# Analog_Input.net
KiCad netlist of a schematic drawn in Altium Designer
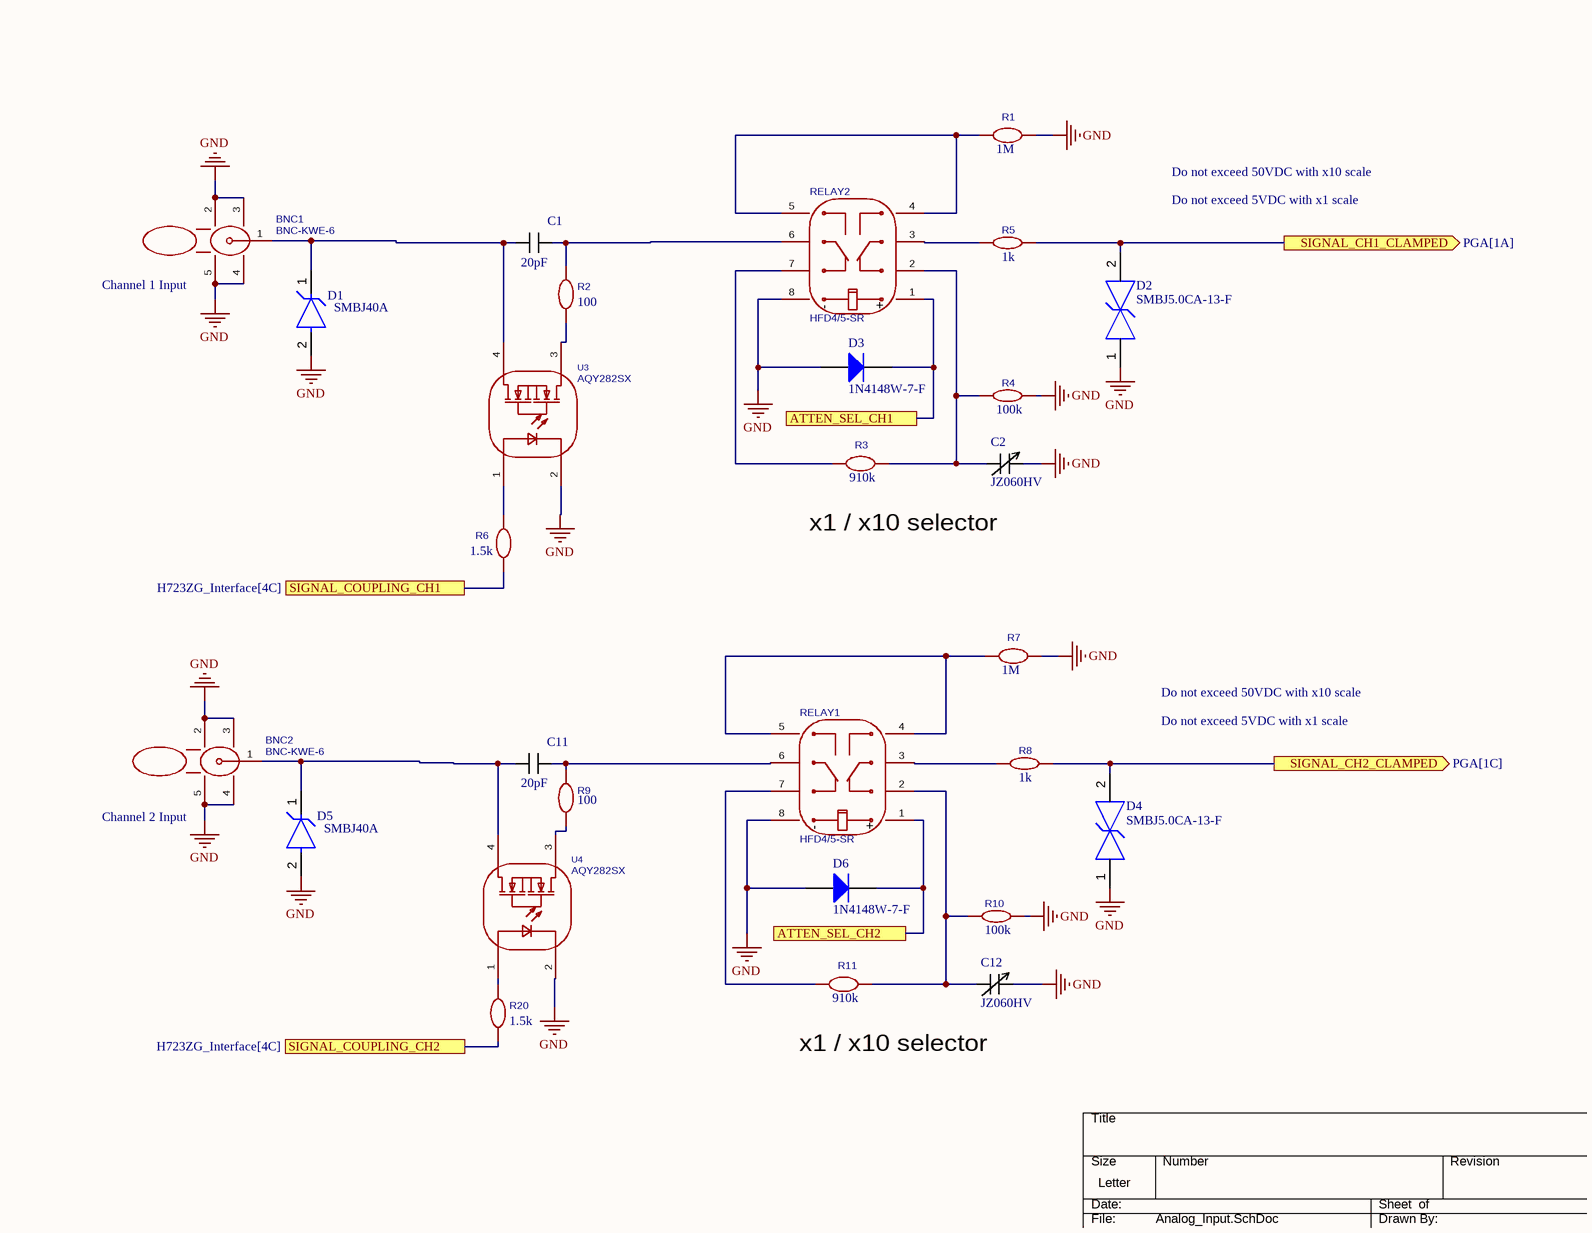
[diagram p0: Analog_Input.SchDoc]

(export (version "E")
  (design (tool "Eeschema 10.0.6"))
  (components
    (comp (ref "BNC1")
      (value "BNC-KWE-6")
      (footprint "CONN-TH_BNC-KWE-6")
      (fields (field (name "MANUFACTURER") "cntitle(中戈泰斗)"))
      (libsource (lib "zhiming xue") (part "BNC-KWE-6"))
    )
    (comp (ref "BNC2")
      (value "BNC-KWE-6")
      (footprint "CONN-TH_BNC-KWE-6")
      (fields (field (name "MANUFACTURER") "cntitle(中戈泰斗)"))
      (libsource (lib "zhiming xue") (part "BNC-KWE-6"))
    )
    (comp (ref "C1")
      (value "20pF")
      (footprint "CAPCP2012X150N")
      (description "Mlcc 20PF ±5% C0G(NP0) 50V 0805")
      (fields
        (field (name "MANUFACTURER") "CCTC")
        (field (name "MANUFACTURER PART NUMBER") "TCC0805COG200J500BT")
      )
      (libsource (lib "zhiming xue") (part "Capacitor"))
    )
    (comp (ref "C2")
      (value "JZ060HV")
      (footprint "CAPCP4914X60N")
      (description "Variable Capacitor, 350V, 2pF Min, 6pF Max, Vertical Adjuster, Surface Mount")
      (libsource (lib "zhiming xue") (part "JZ060HV 2 - 6pF"))
    )
    (comp (ref "C11")
      (value "20pF")
      (footprint "CAPCP2012X150N")
      (description "Mlcc 20PF ±5% C0G(NP0) 50V 0805")
      (fields
        (field (name "MANUFACTURER") "CCTC")
        (field (name "MANUFACTURER PART NUMBER") "TCC0805COG200J500BT")
      )
      (libsource (lib "zhiming xue") (part "Capacitor"))
    )
    (comp (ref "C12")
      (value "JZ060HV")
      (footprint "CAPCP4914X60N")
      (description "Variable Capacitor, 350V, 2pF Min, 6pF Max, Vertical Adjuster, Surface Mount")
      (libsource (lib "zhiming xue") (part "JZ060HV 2 - 6pF"))
    )
    (comp (ref "D1")
      (value "SMBJ40A")
      (footprint "FP-SMBJ-MFG")
      (description "TVS DIODE 40VWM 64.5VC DO214AA")
      (libsource (lib "Altium Content Vault") (part "f813f71cba58e380607f5dd3caf9714"))
    )
    (comp (ref "D2")
      (value "SMBJ5.0CA-13-F")
      (footprint "FP-SMB-CA-MFG")
      (description "TVS DIODE 5V 9.2V SMB")
      (fields
        (field (name "MANUFACTURER") "Diodes Inc")
        (field (name "OCTOPART") "https://octopart.com/smbj5.0ca-13-f-diodes+inc.-13025192")
      )
      (libsource (lib "Altium Content Vault") (part "876f4347bf90aa6f500f43e3cd03972"))
    )
    (comp (ref "D3")
      (value "1N4148W-7-F")
      (footprint "DIOD-SOD123-2_V")
      (description "Fast Switching Diode, 100 V, 0.15 A, -65 to 150 degC, 2-Pin?SOD123, RoHS, Tape and Reel")
      (fields (field (name "MANUFACTURER") "Diodes Inc"))
      (libsource (lib "Altium Content Vault") (part "D-AK-2"))
    )
    (comp (ref "D4")
      (value "SMBJ5.0CA-13-F")
      (footprint "FP-SMB-CA-MFG")
      (description "TVS DIODE 5V 9.2V SMB")
      (fields
        (field (name "MANUFACTURER") "Diodes Inc")
        (field (name "OCTOPART") "https://octopart.com/smbj5.0ca-13-f-diodes+inc.-13025192")
      )
      (libsource (lib "Altium Content Vault") (part "876f4347bf90aa6f500f43e3cd03972"))
    )
    (comp (ref "D5")
      (value "SMBJ40A")
      (footprint "FP-SMBJ-MFG")
      (description "TVS DIODE 40VWM 64.5VC DO214AA")
      (libsource (lib "Altium Content Vault") (part "f813f71cba58e380607f5dd3caf9714"))
    )
    (comp (ref "D6")
      (value "1N4148W-7-F")
      (footprint "DIOD-SOD123-2_V")
      (description "Fast Switching Diode, 100 V, 0.15 A, -65 to 150 degC, 2-Pin?SOD123, RoHS, Tape and Reel")
      (fields (field (name "MANUFACTURER") "Diodes Inc"))
      (libsource (lib "Altium Content Vault") (part "D-AK-2"))
    )
    (comp (ref "R1")
      (value "1M")
      (footprint "R0805")
      (fields
        (field (name "MANUFACTURER") "FOJAN(富捷)")
        (field (name "TOLERANCE") "1%")
        (field (name "MANUFACTURER PART NUMBER") "FRC0805F1004TS")
      )
      (libsource (lib "zhiming xue") (part "RT0805BRD0710K1L"))
    )
    (comp (ref "R2")
      (value "100")
      (footprint "R0805")
      (fields
        (field (name "MANUFACTURER") "FOJAN(富捷)")
        (field (name "TOLERANCE") "1%")
        (field (name "MANUFACTURER PART NUMBER") "FRC0805F1000TS")
      )
      (libsource (lib "zhiming xue") (part "RT0805BRD0710K1L"))
    )
    (comp (ref "R3")
      (value "910k")
      (footprint "R0805")
      (fields
        (field (name "MANUFACTURER") "FOJAN(富捷)")
        (field (name "TOLERANCE") "1%")
        (field (name "MANUFACTURER PART NUMBER") "FRC0805F9103TS")
      )
      (libsource (lib "zhiming xue") (part "RT0805BRD0710K1L"))
    )
    (comp (ref "R4")
      (value "100k")
      (footprint "R0805")
      (fields
        (field (name "MANUFACTURER") "UNI-ROYAL(厚声)")
        (field (name "TOLERANCE") "1%")
        (field (name "MANUFACTURER PART NUMBER") "0805W8F1003T5E")
      )
      (libsource (lib "zhiming xue") (part "0805W8F0000T5E_C17477"))
    )
    (comp (ref "R5")
      (value "1k")
      (footprint "R0805")
      (fields
        (field (name "MANUFACTURER") "UNI-ROYAL(厚声)")
        (field (name "TOLERANCE") "1%")
        (field (name "MANUFACTURER PART NUMBER") "0805W8F1001T5E")
      )
      (libsource (lib "zhiming xue") (part "0805W8F0000T5E_C17477"))
    )
    (comp (ref "R6")
      (value "1.5k")
      (footprint "R0805")
      (fields
        (field (name "MANUFACTURER") "FOJAN(富捷)")
        (field (name "TOLERANCE") "1%")
        (field (name "MANUFACTURER PART NUMBER") "FRC0805F1501TS")
      )
      (libsource (lib "zhiming xue") (part "RT0805BRD0710K1L"))
    )
    (comp (ref "R7")
      (value "1M")
      (footprint "R0805")
      (fields
        (field (name "MANUFACTURER") "FOJAN(富捷)")
        (field (name "TOLERANCE") "1%")
        (field (name "MANUFACTURER PART NUMBER") "FRC0805F1004TS")
      )
      (libsource (lib "zhiming xue") (part "RT0805BRD0710K1L"))
    )
    (comp (ref "R8")
      (value "1k")
      (footprint "R0805")
      (fields
        (field (name "MANUFACTURER") "UNI-ROYAL(厚声)")
        (field (name "TOLERANCE") "1%")
        (field (name "MANUFACTURER PART NUMBER") "0805W8F1001T5E")
      )
      (libsource (lib "zhiming xue") (part "0805W8F0000T5E_C17477"))
    )
    (comp (ref "R9")
      (value "100")
      (footprint "R0805")
      (fields
        (field (name "MANUFACTURER") "FOJAN(富捷)")
        (field (name "TOLERANCE") "1%")
        (field (name "MANUFACTURER PART NUMBER") "FRC0805F1000TS")
      )
      (libsource (lib "zhiming xue") (part "RT0805BRD0710K1L"))
    )
    (comp (ref "R10")
      (value "100k")
      (footprint "R0805")
      (fields
        (field (name "MANUFACTURER") "UNI-ROYAL(厚声)")
        (field (name "TOLERANCE") "1%")
        (field (name "MANUFACTURER PART NUMBER") "0805W8F1003T5E")
      )
      (libsource (lib "zhiming xue") (part "0805W8F0000T5E_C17477"))
    )
    (comp (ref "R11")
      (value "910k")
      (footprint "R0805")
      (fields
        (field (name "MANUFACTURER") "FOJAN(富捷)")
        (field (name "TOLERANCE") "1%")
        (field (name "MANUFACTURER PART NUMBER") "FRC0805F9103TS")
      )
      (libsource (lib "zhiming xue") (part "RT0805BRD0710K1L"))
    )
    (comp (ref "R20")
      (value "1.5k")
      (footprint "R0805")
      (fields
        (field (name "MANUFACTURER") "FOJAN(富捷)")
        (field (name "TOLERANCE") "1%")
        (field (name "MANUFACTURER PART NUMBER") "FRC0805F1501TS")
      )
      (libsource (lib "zhiming xue") (part "RT0805BRD0710K1L"))
    )
    (comp (ref "RELAY1")
      (value "HFD4/5-SR")
      (footprint "RELAY-SMD_HFD4-5-SR")
      (fields (field (name "MANUFACTURER") "HF(宏发)"))
      (libsource (lib "zhiming xue") (part "HFD4/5-SR"))
    )
    (comp (ref "RELAY2")
      (value "HFD4/5-SR")
      (footprint "RELAY-SMD_HFD4-5-SR")
      (fields (field (name "MANUFACTURER") "HF(宏发)"))
      (libsource (lib "zhiming xue") (part "HFD4/5-SR"))
    )
    (comp (ref "U3")
      (value "AQY282SX")
      (footprint "SOP-4_L4.3-W4.4-P2.54-LS7.0-BL")
      (fields (field (name "MANUFACTURER") "PANASONIC(松下)"))
      (libsource (lib "zhiming xue") (part "AQY282SX"))
    )
    (comp (ref "U4")
      (value "AQY282SX")
      (footprint "SOP-4_L4.3-W4.4-P2.54-LS7.0-BL")
      (fields (field (name "MANUFACTURER") "PANASONIC(松下)"))
      (libsource (lib "zhiming xue") (part "AQY282SX"))
    )
  )
  (nets
    (net (code "1") (name "/ATTEN_SEL_CH1") (class "Default")
      (node (ref "D3") (pin "2") (pinfunction "K_2") (pintype "passive"))
      (node (ref "RELAY2") (pin "1") (pinfunction "1_1") (pintype "passive"))
    )
    (net (code "2") (name "/ATTEN_SEL_CH2") (class "Default")
      (node (ref "D6") (pin "2") (pinfunction "K_2") (pintype "passive"))
      (node (ref "RELAY1") (pin "1") (pinfunction "1_1") (pintype "passive"))
    )
    (net (code "3") (name "/SIGNAL_CH1_CLAMPED") (class "Default")
      (node (ref "D2") (pin "2") (pinfunction "2_2") (pintype "passive"))
      (node (ref "R5") (pin "1") (pinfunction "1_1") (pintype "passive"))
    )
    (net (code "4") (name "/SIGNAL_CH2_CLAMPED") (class "Default")
      (node (ref "D4") (pin "2") (pinfunction "2_2") (pintype "passive"))
      (node (ref "R8") (pin "1") (pinfunction "1_1") (pintype "passive"))
    )
    (net (code "5") (name "/SIGNAL_COUPLING_CH1") (class "Default")
      (node (ref "R6") (pin "1") (pinfunction "1_1") (pintype "passive"))
    )
    (net (code "6") (name "/SIGNAL_COUPLING_CH2") (class "Default")
      (node (ref "R20") (pin "1") (pinfunction "1_1") (pintype "passive"))
    )
    (net (code "7") (name "GND") (class "Default")
      (node (ref "BNC1") (pin "2") (pinfunction "2_2") (pintype "passive"))
      (node (ref "BNC1") (pin "3") (pinfunction "3_3") (pintype "passive"))
      (node (ref "BNC1") (pin "4") (pinfunction "4_4") (pintype "passive"))
      (node (ref "BNC1") (pin "5") (pinfunction "5_5") (pintype "passive"))
      (node (ref "BNC2") (pin "2") (pinfunction "2_2") (pintype "passive"))
      (node (ref "BNC2") (pin "3") (pinfunction "3_3") (pintype "passive"))
      (node (ref "BNC2") (pin "4") (pinfunction "4_4") (pintype "passive"))
      (node (ref "BNC2") (pin "5") (pinfunction "5_5") (pintype "passive"))
      (node (ref "C12") (pin "2") (pinfunction "2_2") (pintype "passive"))
      (node (ref "C2") (pin "2") (pinfunction "2_2") (pintype "passive"))
      (node (ref "D1") (pin "2") (pinfunction "A_2") (pintype "passive"))
      (node (ref "D2") (pin "1") (pinfunction "1_1") (pintype "passive"))
      (node (ref "D3") (pin "1") (pinfunction "A_1") (pintype "passive"))
      (node (ref "D4") (pin "1") (pinfunction "1_1") (pintype "passive"))
      (node (ref "D5") (pin "2") (pinfunction "A_2") (pintype "passive"))
      (node (ref "D6") (pin "1") (pinfunction "A_1") (pintype "passive"))
      (node (ref "R1") (pin "1") (pinfunction "1_1") (pintype "passive"))
      (node (ref "R10") (pin "1") (pinfunction "1_1") (pintype "passive"))
      (node (ref "R4") (pin "1") (pinfunction "1_1") (pintype "passive"))
      (node (ref "R7") (pin "1") (pinfunction "1_1") (pintype "passive"))
      (node (ref "RELAY1") (pin "8") (pinfunction "8_8") (pintype "passive"))
      (node (ref "RELAY2") (pin "8") (pinfunction "8_8") (pintype "passive"))
      (node (ref "U3") (pin "2") (pinfunction "2_2") (pintype "passive"))
      (node (ref "U4") (pin "2") (pinfunction "2_2") (pintype "passive"))
    )
    (net (code "8") (name "Net-(C1-Pad2)") (class "Default")
      (node (ref "C1") (pin "2") (pinfunction "2_2") (pintype "passive"))
      (node (ref "R2") (pin "2") (pinfunction "2_2") (pintype "passive"))
      (node (ref "RELAY2") (pin "6") (pinfunction "6_6") (pintype "passive"))
    )
    (net (code "9") (name "Net-(C2-Pad1)") (class "Default")
      (node (ref "C2") (pin "1") (pinfunction "1_1") (pintype "passive"))
      (node (ref "R3") (pin "1") (pinfunction "1_1") (pintype "passive"))
      (node (ref "R4") (pin "2") (pinfunction "2_2") (pintype "passive"))
      (node (ref "RELAY2") (pin "2") (pinfunction "2_2") (pintype "passive"))
    )
    (net (code "10") (name "Net-(C11-Pad2)") (class "Default")
      (node (ref "C11") (pin "2") (pinfunction "2_2") (pintype "passive"))
      (node (ref "R9") (pin "2") (pinfunction "2_2") (pintype "passive"))
      (node (ref "RELAY1") (pin "6") (pinfunction "6_6") (pintype "passive"))
    )
    (net (code "11") (name "Net-(C12-Pad1)") (class "Default")
      (node (ref "C12") (pin "1") (pinfunction "1_1") (pintype "passive"))
      (node (ref "R10") (pin "2") (pinfunction "2_2") (pintype "passive"))
      (node (ref "R11") (pin "1") (pinfunction "1_1") (pintype "passive"))
      (node (ref "RELAY1") (pin "2") (pinfunction "2_2") (pintype "passive"))
    )
    (net (code "12") (name "Net-(D1-C)") (class "Default")
      (node (ref "BNC1") (pin "1") (pinfunction "1_1") (pintype "passive"))
      (node (ref "C1") (pin "1") (pinfunction "1_1") (pintype "passive"))
      (node (ref "D1") (pin "1") (pinfunction "C_1") (pintype "passive"))
      (node (ref "U3") (pin "4") (pinfunction "4_4") (pintype "passive"))
    )
    (net (code "13") (name "Net-(D5-C)") (class "Default")
      (node (ref "BNC2") (pin "1") (pinfunction "1_1") (pintype "passive"))
      (node (ref "C11") (pin "1") (pinfunction "1_1") (pintype "passive"))
      (node (ref "D5") (pin "1") (pinfunction "C_1") (pintype "passive"))
      (node (ref "U4") (pin "4") (pinfunction "4_4") (pintype "passive"))
    )
    (net (code "14") (name "Net-(R1-Pad2)") (class "Default")
      (node (ref "R1") (pin "2") (pinfunction "2_2") (pintype "passive"))
      (node (ref "RELAY2") (pin "4") (pinfunction "4_4") (pintype "passive"))
      (node (ref "RELAY2") (pin "5") (pinfunction "5_5") (pintype "passive"))
    )
    (net (code "15") (name "Net-(R2-Pad1)") (class "Default")
      (node (ref "R2") (pin "1") (pinfunction "1_1") (pintype "passive"))
      (node (ref "U3") (pin "3") (pinfunction "3_3") (pintype "passive"))
    )
    (net (code "16") (name "Net-(R3-Pad2)") (class "Default")
      (node (ref "R3") (pin "2") (pinfunction "2_2") (pintype "passive"))
      (node (ref "RELAY2") (pin "7") (pinfunction "7_7") (pintype "passive"))
    )
    (net (code "17") (name "Net-(R5-Pad2)") (class "Default")
      (node (ref "R5") (pin "2") (pinfunction "2_2") (pintype "passive"))
      (node (ref "RELAY2") (pin "3") (pinfunction "3_3") (pintype "passive"))
    )
    (net (code "18") (name "Net-(R6-Pad2)") (class "Default")
      (node (ref "R6") (pin "2") (pinfunction "2_2") (pintype "passive"))
      (node (ref "U3") (pin "1") (pinfunction "1_1") (pintype "passive"))
    )
    (net (code "19") (name "Net-(R7-Pad2)") (class "Default")
      (node (ref "R7") (pin "2") (pinfunction "2_2") (pintype "passive"))
      (node (ref "RELAY1") (pin "4") (pinfunction "4_4") (pintype "passive"))
      (node (ref "RELAY1") (pin "5") (pinfunction "5_5") (pintype "passive"))
    )
    (net (code "20") (name "Net-(R8-Pad2)") (class "Default")
      (node (ref "R8") (pin "2") (pinfunction "2_2") (pintype "passive"))
      (node (ref "RELAY1") (pin "3") (pinfunction "3_3") (pintype "passive"))
    )
    (net (code "21") (name "Net-(R9-Pad1)") (class "Default")
      (node (ref "R9") (pin "1") (pinfunction "1_1") (pintype "passive"))
      (node (ref "U4") (pin "3") (pinfunction "3_3") (pintype "passive"))
    )
    (net (code "22") (name "Net-(R11-Pad2)") (class "Default")
      (node (ref "R11") (pin "2") (pinfunction "2_2") (pintype "passive"))
      (node (ref "RELAY1") (pin "7") (pinfunction "7_7") (pintype "passive"))
    )
    (net (code "23") (name "Net-(R20-Pad2)") (class "Default")
      (node (ref "R20") (pin "2") (pinfunction "2_2") (pintype "passive"))
      (node (ref "U4") (pin "1") (pinfunction "1_1") (pintype "passive"))
    )
  )
)
